# l293d.net
KiCad netlist of a schematic drawn in EAGLE
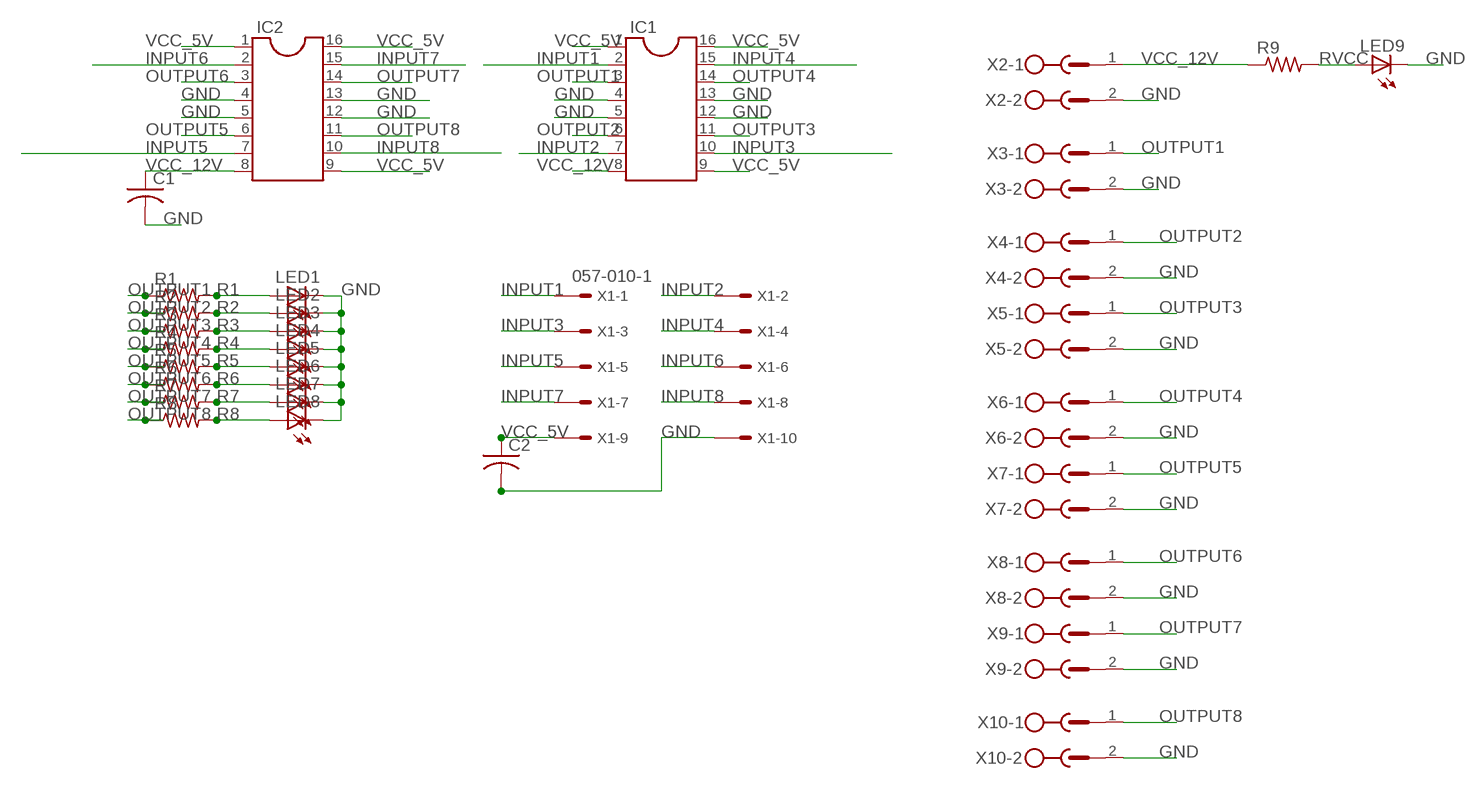
[diagram p0: schematic, sheet 1]

(export (version "E")
  (design (tool "Eeschema 10.0.6"))
  (components
    (comp (ref "C1")
      (value "C-US050-025X075")
      (footprint "eagle-import:C050-025X075")
      (libsource (lib "eagle-import") (part "C-US050-025X075"))
    )
    (comp (ref "C2")
      (value "C-US050-025X075")
      (footprint "eagle-import:C050-025X075")
      (libsource (lib "eagle-import") (part "C-US050-025X075"))
    )
    (comp (ref "IC1")
      (value "DIL16S")
      (footprint "eagle-import:SOCKET-16")
      (libsource (lib "eagle-import") (part "DIL16S"))
    )
    (comp (ref "IC2")
      (value "DIL16S")
      (footprint "eagle-import:SOCKET-16")
      (libsource (lib "eagle-import") (part "DIL16S"))
    )
    (comp (ref "LED1")
      (value "LED3MM")
      (footprint "eagle-import:LED3MM")
      (libsource (lib "eagle-import") (part "LED3MM"))
    )
    (comp (ref "LED2")
      (value "LED3MM")
      (footprint "eagle-import:LED3MM")
      (libsource (lib "eagle-import") (part "LED3MM"))
    )
    (comp (ref "LED3")
      (value "LED3MM")
      (footprint "eagle-import:LED3MM")
      (libsource (lib "eagle-import") (part "LED3MM"))
    )
    (comp (ref "LED4")
      (value "LED3MM")
      (footprint "eagle-import:LED3MM")
      (libsource (lib "eagle-import") (part "LED3MM"))
    )
    (comp (ref "LED5")
      (value "LED3MM")
      (footprint "eagle-import:LED3MM")
      (libsource (lib "eagle-import") (part "LED3MM"))
    )
    (comp (ref "LED6")
      (value "LED3MM")
      (footprint "eagle-import:LED3MM")
      (libsource (lib "eagle-import") (part "LED3MM"))
    )
    (comp (ref "LED7")
      (value "LED3MM")
      (footprint "eagle-import:LED3MM")
      (libsource (lib "eagle-import") (part "LED3MM"))
    )
    (comp (ref "LED8")
      (value "LED3MM")
      (footprint "eagle-import:LED3MM")
      (libsource (lib "eagle-import") (part "LED3MM"))
    )
    (comp (ref "LED9")
      (value "LED3MM")
      (footprint "eagle-import:LED3MM")
      (libsource (lib "eagle-import") (part "LED3MM"))
    )
    (comp (ref "R1")
      (value "R-US_0204/7")
      (footprint "eagle-import:0204_7")
      (libsource (lib "eagle-import") (part "R-US_0204/7"))
    )
    (comp (ref "R2")
      (value "R-US_0204/7")
      (footprint "eagle-import:0204_7")
      (libsource (lib "eagle-import") (part "R-US_0204/7"))
    )
    (comp (ref "R3")
      (value "R-US_0204/7")
      (footprint "eagle-import:0204_7")
      (libsource (lib "eagle-import") (part "R-US_0204/7"))
    )
    (comp (ref "R4")
      (value "R-US_0204/7")
      (footprint "eagle-import:0204_7")
      (libsource (lib "eagle-import") (part "R-US_0204/7"))
    )
    (comp (ref "R5")
      (value "R-US_0204/7")
      (footprint "eagle-import:0204_7")
      (libsource (lib "eagle-import") (part "R-US_0204/7"))
    )
    (comp (ref "R6")
      (value "R-US_0204/7")
      (footprint "eagle-import:0204_7")
      (libsource (lib "eagle-import") (part "R-US_0204/7"))
    )
    (comp (ref "R7")
      (value "R-US_0204/7")
      (footprint "eagle-import:0204_7")
      (libsource (lib "eagle-import") (part "R-US_0204/7"))
    )
    (comp (ref "R8")
      (value "R-US_0204/7")
      (footprint "eagle-import:0204_7")
      (libsource (lib "eagle-import") (part "R-US_0204/7"))
    )
    (comp (ref "R9")
      (value "R-US_0204/7")
      (footprint "eagle-import:0204_7")
      (libsource (lib "eagle-import") (part "R-US_0204/7"))
    )
    (comp (ref "X1")
      (value "057-010-1")
      (footprint "eagle-import:057-010-1")
      (libsource (lib "eagle-import") (part "057-010-1"))
    )
    (comp (ref "X2")
      (value "MSTBV2")
      (footprint "eagle-import:MSTBV2")
      (libsource (lib "eagle-import") (part "MSTBV2"))
    )
    (comp (ref "X3")
      (value "MSTBV2")
      (footprint "eagle-import:MSTBV2")
      (libsource (lib "eagle-import") (part "MSTBV2"))
    )
    (comp (ref "X4")
      (value "MSTBV2")
      (footprint "eagle-import:MSTBV2")
      (libsource (lib "eagle-import") (part "MSTBV2"))
    )
    (comp (ref "X5")
      (value "MSTBV2")
      (footprint "eagle-import:MSTBV2")
      (libsource (lib "eagle-import") (part "MSTBV2"))
    )
    (comp (ref "X6")
      (value "MSTBV2")
      (footprint "eagle-import:MSTBV2")
      (libsource (lib "eagle-import") (part "MSTBV2"))
    )
    (comp (ref "X7")
      (value "MSTBV2")
      (footprint "eagle-import:MSTBV2")
      (libsource (lib "eagle-import") (part "MSTBV2"))
    )
    (comp (ref "X8")
      (value "MSTBV2")
      (footprint "eagle-import:MSTBV2")
      (libsource (lib "eagle-import") (part "MSTBV2"))
    )
    (comp (ref "X9")
      (value "MSTBV2")
      (footprint "eagle-import:MSTBV2")
      (libsource (lib "eagle-import") (part "MSTBV2"))
    )
    (comp (ref "X10")
      (value "MSTBV2")
      (footprint "eagle-import:MSTBV2")
      (libsource (lib "eagle-import") (part "MSTBV2"))
    )
  )
  (nets
    (net (code "1") (name "/GND") (class "Default")
      (node (ref "C1") (pin "2") (pinfunction "2_2") (pintype "passive"))
      (node (ref "C2") (pin "2") (pinfunction "2_2") (pintype "passive"))
      (node (ref "IC1") (pin "12") (pinfunction "12_12") (pintype "passive"))
      (node (ref "IC1") (pin "13") (pinfunction "13_13") (pintype "passive"))
      (node (ref "IC1") (pin "4") (pinfunction "4_4") (pintype "passive"))
      (node (ref "IC1") (pin "5") (pinfunction "5_5") (pintype "passive"))
      (node (ref "IC2") (pin "12") (pinfunction "12_12") (pintype "passive"))
      (node (ref "IC2") (pin "13") (pinfunction "13_13") (pintype "passive"))
      (node (ref "IC2") (pin "4") (pinfunction "4_4") (pintype "passive"))
      (node (ref "IC2") (pin "5") (pinfunction "5_5") (pintype "passive"))
      (node (ref "LED1") (pin "K") (pinfunction "C_K") (pintype "passive"))
      (node (ref "LED2") (pin "K") (pinfunction "C_K") (pintype "passive"))
      (node (ref "LED3") (pin "K") (pinfunction "C_K") (pintype "passive"))
      (node (ref "LED4") (pin "K") (pinfunction "C_K") (pintype "passive"))
      (node (ref "LED5") (pin "K") (pinfunction "C_K") (pintype "passive"))
      (node (ref "LED6") (pin "K") (pinfunction "C_K") (pintype "passive"))
      (node (ref "LED7") (pin "K") (pinfunction "C_K") (pintype "passive"))
      (node (ref "LED8") (pin "K") (pinfunction "C_K") (pintype "passive"))
      (node (ref "LED9") (pin "K") (pinfunction "C_K") (pintype "passive"))
      (node (ref "X1") (pin "10") (pinfunction "S_10") (pintype "passive"))
      (node (ref "X10") (pin "2") (pinfunction "SK_2") (pintype "passive"))
      (node (ref "X2") (pin "2") (pinfunction "SK_2") (pintype "passive"))
      (node (ref "X3") (pin "2") (pinfunction "SK_2") (pintype "passive"))
      (node (ref "X4") (pin "2") (pinfunction "SK_2") (pintype "passive"))
      (node (ref "X5") (pin "2") (pinfunction "SK_2") (pintype "passive"))
      (node (ref "X6") (pin "2") (pinfunction "SK_2") (pintype "passive"))
      (node (ref "X7") (pin "2") (pinfunction "SK_2") (pintype "passive"))
      (node (ref "X8") (pin "2") (pinfunction "SK_2") (pintype "passive"))
      (node (ref "X9") (pin "2") (pinfunction "SK_2") (pintype "passive"))
    )
    (net (code "2") (name "/INPUT1") (class "Default")
      (node (ref "IC1") (pin "2") (pinfunction "2_2") (pintype "passive"))
      (node (ref "X1") (pin "1") (pinfunction "S_1") (pintype "passive"))
    )
    (net (code "3") (name "/INPUT2") (class "Default")
      (node (ref "IC1") (pin "7") (pinfunction "7_7") (pintype "passive"))
      (node (ref "X1") (pin "2") (pinfunction "S_2") (pintype "passive"))
    )
    (net (code "4") (name "/INPUT3") (class "Default")
      (node (ref "IC1") (pin "10") (pinfunction "10_10") (pintype "passive"))
      (node (ref "X1") (pin "3") (pinfunction "S_3") (pintype "passive"))
    )
    (net (code "5") (name "/INPUT4") (class "Default")
      (node (ref "IC1") (pin "15") (pinfunction "15_15") (pintype "passive"))
      (node (ref "X1") (pin "4") (pinfunction "S_4") (pintype "passive"))
    )
    (net (code "6") (name "/INPUT5") (class "Default")
      (node (ref "IC2") (pin "7") (pinfunction "7_7") (pintype "passive"))
      (node (ref "X1") (pin "5") (pinfunction "S_5") (pintype "passive"))
    )
    (net (code "7") (name "/INPUT6") (class "Default")
      (node (ref "IC2") (pin "2") (pinfunction "2_2") (pintype "passive"))
      (node (ref "X1") (pin "6") (pinfunction "S_6") (pintype "passive"))
    )
    (net (code "8") (name "/INPUT7") (class "Default")
      (node (ref "IC2") (pin "15") (pinfunction "15_15") (pintype "passive"))
      (node (ref "X1") (pin "7") (pinfunction "S_7") (pintype "passive"))
    )
    (net (code "9") (name "/INPUT8") (class "Default")
      (node (ref "IC2") (pin "10") (pinfunction "10_10") (pintype "passive"))
      (node (ref "X1") (pin "8") (pinfunction "S_8") (pintype "passive"))
    )
    (net (code "10") (name "/OUTPUT1") (class "Default")
      (node (ref "IC1") (pin "3") (pinfunction "3_3") (pintype "passive"))
      (node (ref "R1") (pin "1") (pinfunction "1_1") (pintype "passive"))
      (node (ref "X3") (pin "1") (pinfunction "SK_1") (pintype "passive"))
    )
    (net (code "11") (name "/OUTPUT2") (class "Default")
      (node (ref "IC1") (pin "6") (pinfunction "6_6") (pintype "passive"))
      (node (ref "R2") (pin "1") (pinfunction "1_1") (pintype "passive"))
      (node (ref "X4") (pin "1") (pinfunction "SK_1") (pintype "passive"))
    )
    (net (code "12") (name "/OUTPUT3") (class "Default")
      (node (ref "IC1") (pin "11") (pinfunction "11_11") (pintype "passive"))
      (node (ref "R3") (pin "1") (pinfunction "1_1") (pintype "passive"))
      (node (ref "X5") (pin "1") (pinfunction "SK_1") (pintype "passive"))
    )
    (net (code "13") (name "/OUTPUT4") (class "Default")
      (node (ref "IC1") (pin "14") (pinfunction "14_14") (pintype "passive"))
      (node (ref "R4") (pin "1") (pinfunction "1_1") (pintype "passive"))
      (node (ref "X6") (pin "1") (pinfunction "SK_1") (pintype "passive"))
    )
    (net (code "14") (name "/OUTPUT5") (class "Default")
      (node (ref "IC2") (pin "6") (pinfunction "6_6") (pintype "passive"))
      (node (ref "R5") (pin "1") (pinfunction "1_1") (pintype "passive"))
      (node (ref "X7") (pin "1") (pinfunction "SK_1") (pintype "passive"))
    )
    (net (code "15") (name "/OUTPUT6") (class "Default")
      (node (ref "IC2") (pin "3") (pinfunction "3_3") (pintype "passive"))
      (node (ref "R6") (pin "1") (pinfunction "1_1") (pintype "passive"))
      (node (ref "X8") (pin "1") (pinfunction "SK_1") (pintype "passive"))
    )
    (net (code "16") (name "/OUTPUT7") (class "Default")
      (node (ref "IC2") (pin "14") (pinfunction "14_14") (pintype "passive"))
      (node (ref "R7") (pin "1") (pinfunction "1_1") (pintype "passive"))
      (node (ref "X9") (pin "1") (pinfunction "SK_1") (pintype "passive"))
    )
    (net (code "17") (name "/OUTPUT8") (class "Default")
      (node (ref "IC2") (pin "11") (pinfunction "11_11") (pintype "passive"))
      (node (ref "R8") (pin "1") (pinfunction "1_1") (pintype "passive"))
      (node (ref "X10") (pin "1") (pinfunction "SK_1") (pintype "passive"))
    )
    (net (code "18") (name "/R1") (class "Default")
      (node (ref "LED1") (pin "A") (pinfunction "A_A") (pintype "passive"))
      (node (ref "R1") (pin "2") (pinfunction "2_2") (pintype "passive"))
    )
    (net (code "19") (name "/R2") (class "Default")
      (node (ref "LED2") (pin "A") (pinfunction "A_A") (pintype "passive"))
      (node (ref "R2") (pin "2") (pinfunction "2_2") (pintype "passive"))
    )
    (net (code "20") (name "/R3") (class "Default")
      (node (ref "LED3") (pin "A") (pinfunction "A_A") (pintype "passive"))
      (node (ref "R3") (pin "2") (pinfunction "2_2") (pintype "passive"))
    )
    (net (code "21") (name "/R4") (class "Default")
      (node (ref "LED4") (pin "A") (pinfunction "A_A") (pintype "passive"))
      (node (ref "R4") (pin "2") (pinfunction "2_2") (pintype "passive"))
    )
    (net (code "22") (name "/R5") (class "Default")
      (node (ref "LED5") (pin "A") (pinfunction "A_A") (pintype "passive"))
      (node (ref "R5") (pin "2") (pinfunction "2_2") (pintype "passive"))
    )
    (net (code "23") (name "/R6") (class "Default")
      (node (ref "LED6") (pin "A") (pinfunction "A_A") (pintype "passive"))
      (node (ref "R6") (pin "2") (pinfunction "2_2") (pintype "passive"))
    )
    (net (code "24") (name "/R7") (class "Default")
      (node (ref "LED7") (pin "A") (pinfunction "A_A") (pintype "passive"))
      (node (ref "R7") (pin "2") (pinfunction "2_2") (pintype "passive"))
    )
    (net (code "25") (name "/R8") (class "Default")
      (node (ref "LED8") (pin "A") (pinfunction "A_A") (pintype "passive"))
      (node (ref "R8") (pin "2") (pinfunction "2_2") (pintype "passive"))
    )
    (net (code "26") (name "/RVCC") (class "Default")
      (node (ref "LED9") (pin "A") (pinfunction "A_A") (pintype "passive"))
      (node (ref "R9") (pin "2") (pinfunction "2_2") (pintype "passive"))
    )
    (net (code "27") (name "/VCC_5V") (class "Default")
      (node (ref "C2") (pin "1") (pinfunction "1_1") (pintype "passive"))
      (node (ref "IC1") (pin "1") (pinfunction "1_1") (pintype "passive"))
      (node (ref "IC1") (pin "16") (pinfunction "16_16") (pintype "passive"))
      (node (ref "IC1") (pin "9") (pinfunction "9_9") (pintype "passive"))
      (node (ref "IC2") (pin "1") (pinfunction "1_1") (pintype "passive"))
      (node (ref "IC2") (pin "16") (pinfunction "16_16") (pintype "passive"))
      (node (ref "IC2") (pin "9") (pinfunction "9_9") (pintype "passive"))
      (node (ref "X1") (pin "9") (pinfunction "S_9") (pintype "passive"))
    )
    (net (code "28") (name "/VCC_12V") (class "Default")
      (node (ref "C1") (pin "1") (pinfunction "1_1") (pintype "passive"))
      (node (ref "IC1") (pin "8") (pinfunction "8_8") (pintype "passive"))
      (node (ref "IC2") (pin "8") (pinfunction "8_8") (pintype "passive"))
      (node (ref "R9") (pin "1") (pinfunction "1_1") (pintype "passive"))
      (node (ref "X2") (pin "1") (pinfunction "SK_1") (pintype "passive"))
    )
  )
)
